# acquisition.net
KiCad netlist of a schematic drawn in Altium Designer
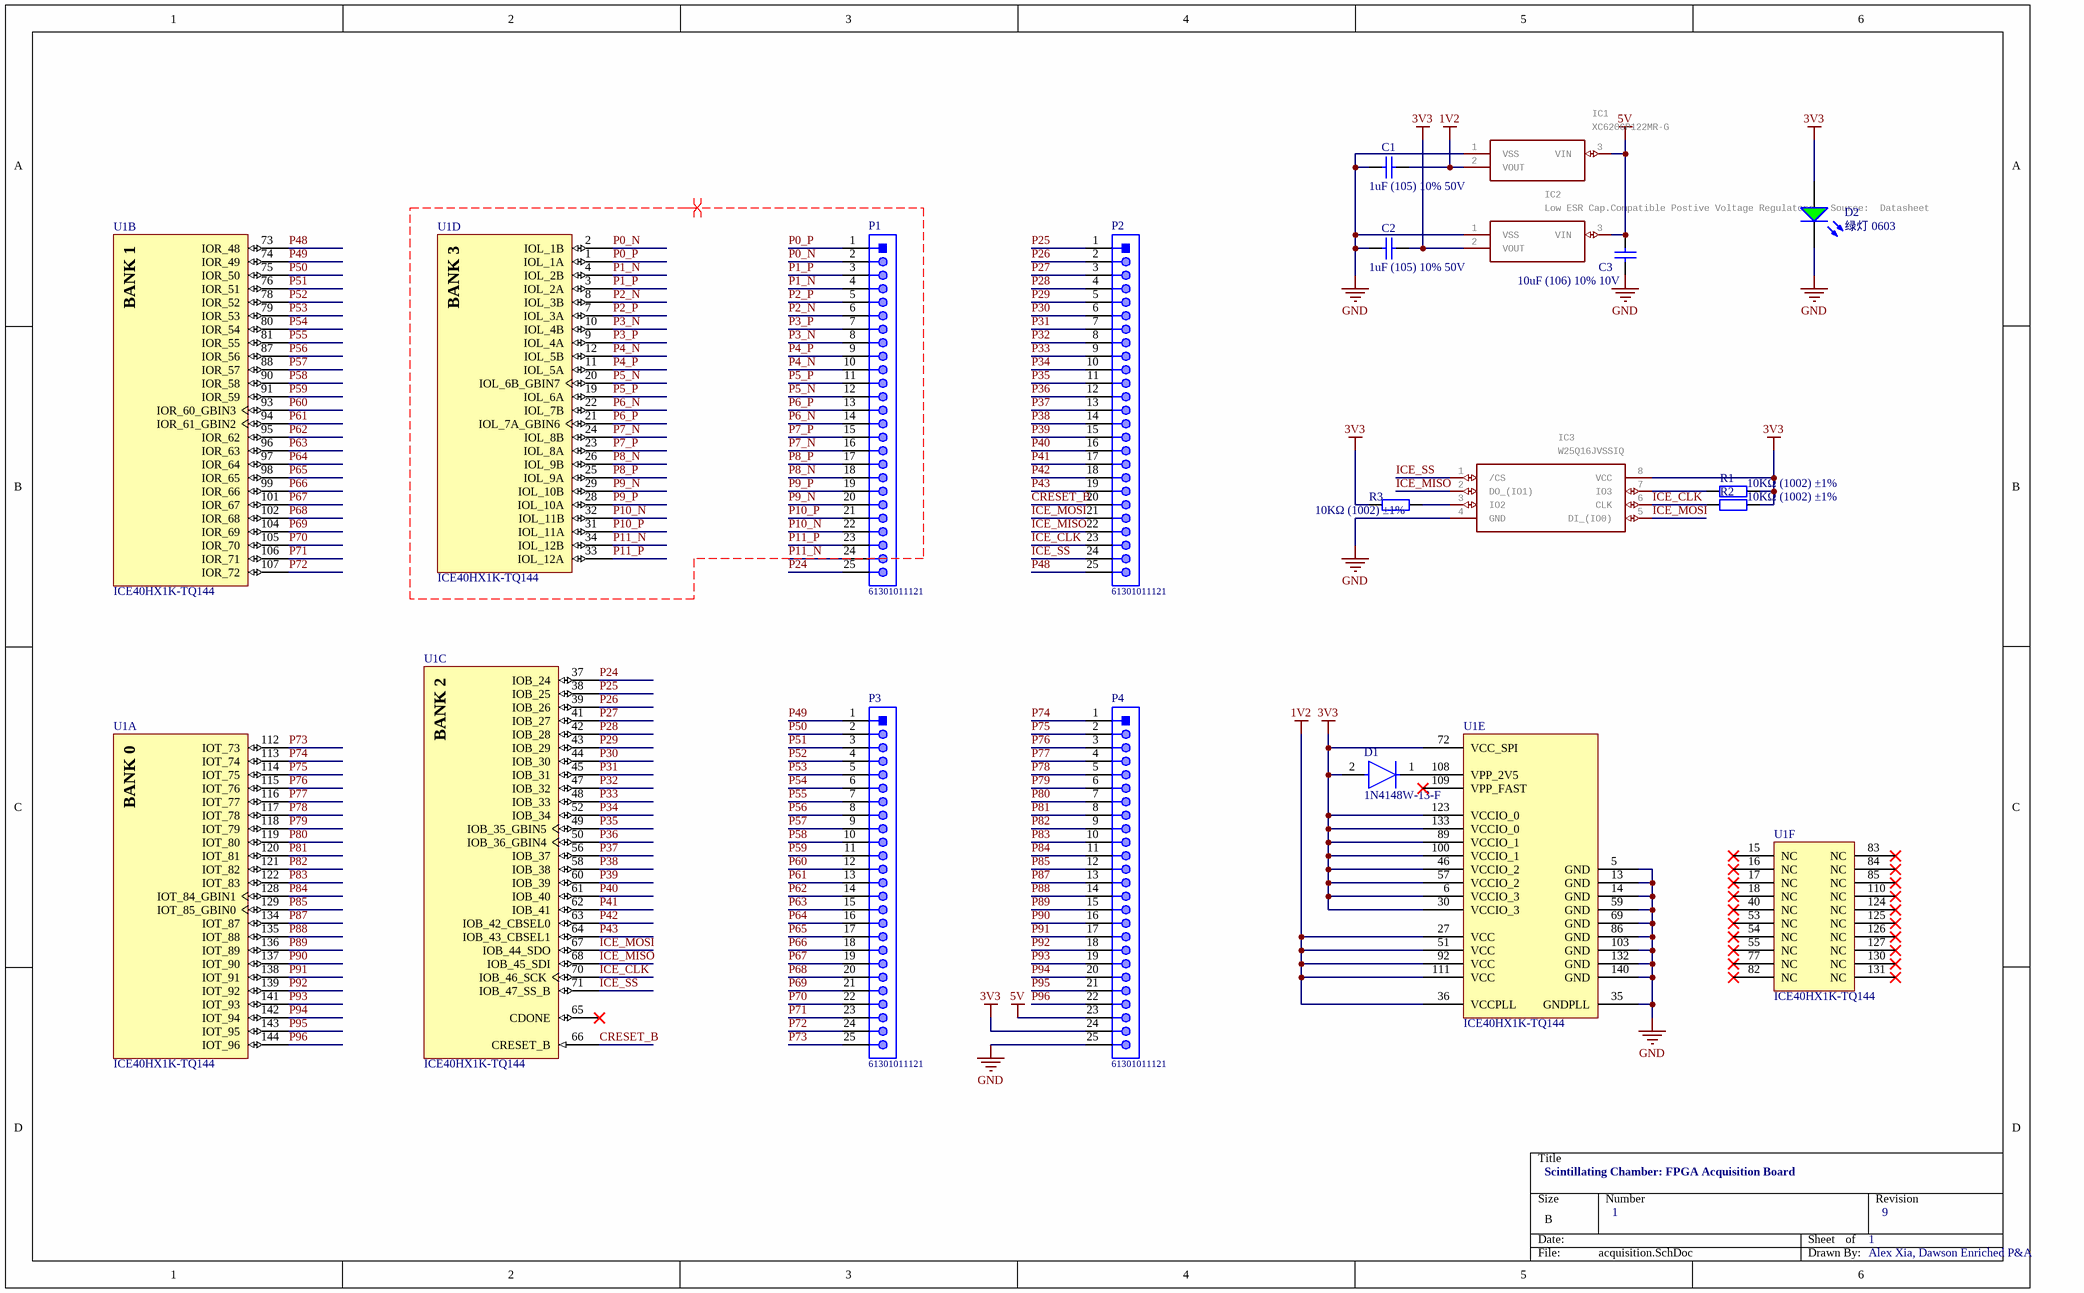
[diagram p0: acquisition.SchDoc]

(export (version "E")
  (design (tool "Eeschema 10.0.6"))
  (components
    (comp (ref "C1")
      (value "1uF (105) 10% 50V")
      (footprint "0603_C")
      (description "贴片电容")
      (libsource (lib "Cap") (part "0603 1uF (105) 10% 50V"))
    )
    (comp (ref "C2")
      (value "1uF (105) 10% 50V")
      (footprint "0603_C")
      (description "贴片电容")
      (libsource (lib "Cap") (part "0603 1uF (105) 10% 50V"))
    )
    (comp (ref "C3")
      (value "10uF (106) 10% 10V")
      (footprint "0603_C")
      (description "贴片电容")
      (libsource (lib "Cap") (part "0603 10uF (106) 10% 10V"))
    )
    (comp (ref "D1")
      (value "1N4148W-13-F")
      (footprint "FP-SOD123-MFG")
      (description "DIODE GEN PURP 100V 150MA SOD123")
      (fields
        (field (name "OCTOPART") "https://octopart.com/1n4148w-13-f-diodes+inc.-2359612")
        (field (name "MANUFACTURER") "Diodes Inc.")
      )
      (libsource (lib "Altium Content Vault") (part "d7152d700b627762746794eb795d46e"))
    )
    (comp (ref "D2")
      (value "绿灯 0603")
      (footprint "0603_LED_S1")
      (description "发光二极管")
      (libsource (lib "LED") (part "0603 绿灯"))
    )
    (comp (ref "IC1")
      (value "XC6206P122MR-G")
      (footprint "SOT95P280X130-3N")
      (fields (field (name "MOUSER_PART_NUMBER") "865-XC6206P122MR-G"))
      (libsource (lib "XC6206P122MR-G") (part "XC6206P122MR-G"))
    )
    (comp (ref "IC2")
      (value "Low ESR Cap.Compatible Postive Voltage Regulators   Source:  Datasheet")
      (footprint "SOT95P280X130-3N")
      (fields (field (name "MANUFACTURER_PART_NUMBER") "XC6206P332MR"))
      (libsource (lib "XC6206P332MR") (part "XC6206P332MR"))
    )
    (comp (ref "IC3")
      (value "W25Q16JVSSIQ")
      (footprint "SOIC127P790X216-8N")
      (fields (field (name "MOUSER_PART_NUMBER") "454-W25Q16JVSSIQ"))
      (libsource (lib "W25Q16JVSSIQ") (part "W25Q16JVSSIQ"))
    )
    (comp (ref "P1")
      (value "61301011121")
      (footprint "61301011121")
      (description "THT Vertical Pin Header WR-PHD, Pitch 2.54 mm, Single Row, 25 pins")
      (libsource (lib "headers") (part "header"))
    )
    (comp (ref "P2")
      (value "61301011121")
      (footprint "61301011121")
      (description "THT Vertical Pin Header WR-PHD, Pitch 2.54 mm, Single Row, 25 pins")
      (libsource (lib "headers") (part "header"))
    )
    (comp (ref "P3")
      (value "61301011121")
      (footprint "61301011121")
      (description "THT Vertical Pin Header WR-PHD, Pitch 2.54 mm, Single Row, 25 pins")
      (libsource (lib "headers") (part "header"))
    )
    (comp (ref "P4")
      (value "61301011121")
      (footprint "61301011121")
      (description "THT Vertical Pin Header WR-PHD, Pitch 2.54 mm, Single Row, 25 pins")
      (libsource (lib "headers") (part "header"))
    )
    (comp (ref "R1")
      (value "10KΩ (1002) ±1%")
      (footprint "0603_R")
      (description "贴片电阻")
      (libsource (lib "RES") (part "0603 10KΩ (1002) 1%"))
    )
    (comp (ref "R2")
      (value "10KΩ (1002) ±1%")
      (footprint "0603_R")
      (description "贴片电阻")
      (libsource (lib "RES") (part "0603 10KΩ (1002) 1%"))
    )
    (comp (ref "R3")
      (value "10KΩ (1002) ±1%")
      (footprint "0603_R")
      (description "贴片电阻")
      (libsource (lib "RES") (part "0603 10KΩ (1002) 1%"))
    )
    (comp (ref "U1")
      (value "ICE40HX1K-TQ144")
      (footprint "LATC-TQFP-144_L")
      (fields (field (name "MANUFACTURER") "Lattice Semiconductor"))
      (libsource (lib "Altium Content Vault") (part "LATC-HX1K-TQFP-144"))
    )
  )
  (nets
    (net (code "1") (name "/CRESET_B") (class "Default")
      (node (ref "P2") (pin "20") (pinfunction "20_20") (pintype "passive"))
      (node (ref "U1") (pin "66") (pinfunction "CRESET_B_66") (pintype "input"))
    )
    (net (code "2") (name "/ICE_CLK") (class "Default")
      (node (ref "IC3") (pin "6") (pinfunction "CLK_6") (pintype "bidirectional"))
      (node (ref "P2") (pin "23") (pinfunction "23_23") (pintype "passive"))
      (node (ref "R2") (pin "1") (pinfunction "1_1") (pintype "passive"))
      (node (ref "U1") (pin "70") (pinfunction "IOB_46_SCK_70") (pintype "bidirectional"))
    )
    (net (code "3") (name "/ICE_MISO") (class "Default")
      (node (ref "IC3") (pin "2") (pinfunction "DO_(IO1)_2") (pintype "bidirectional"))
      (node (ref "P2") (pin "22") (pinfunction "22_22") (pintype "passive"))
      (node (ref "U1") (pin "68") (pinfunction "IOB_45_SDI_68") (pintype "bidirectional"))
    )
    (net (code "4") (name "/ICE_MOSI") (class "Default")
      (node (ref "IC3") (pin "5") (pinfunction "DI_(IO0)_5") (pintype "bidirectional"))
      (node (ref "P2") (pin "21") (pinfunction "21_21") (pintype "passive"))
      (node (ref "U1") (pin "67") (pinfunction "IOB_44_SDO_67") (pintype "bidirectional"))
    )
    (net (code "5") (name "/ICE_SS") (class "Default")
      (node (ref "IC3") (pin "1") (pinfunction "/CS_1") (pintype "bidirectional"))
      (node (ref "P2") (pin "24") (pinfunction "24_24") (pintype "passive"))
      (node (ref "U1") (pin "71") (pinfunction "IOB_47_SS_B_71") (pintype "bidirectional"))
    )
    (net (code "6") (name "/P0_N") (class "Default")
      (node (ref "P1") (pin "2") (pinfunction "2_2") (pintype "passive"))
      (node (ref "U1") (pin "2") (pinfunction "IOL_1B_2") (pintype "bidirectional"))
    )
    (net (code "7") (name "/P0_P") (class "Default")
      (node (ref "P1") (pin "1") (pinfunction "1_1") (pintype "passive"))
      (node (ref "U1") (pin "1") (pinfunction "IOL_1A_1") (pintype "bidirectional"))
    )
    (net (code "8") (name "/P1_N") (class "Default")
      (node (ref "P1") (pin "4") (pinfunction "4_4") (pintype "passive"))
      (node (ref "U1") (pin "4") (pinfunction "IOL_2B_4") (pintype "bidirectional"))
    )
    (net (code "9") (name "/P1_P") (class "Default")
      (node (ref "P1") (pin "3") (pinfunction "3_3") (pintype "passive"))
      (node (ref "U1") (pin "3") (pinfunction "IOL_2A_3") (pintype "bidirectional"))
    )
    (net (code "10") (name "/P2_N") (class "Default")
      (node (ref "P1") (pin "6") (pinfunction "6_6") (pintype "passive"))
      (node (ref "U1") (pin "8") (pinfunction "IOL_3B_8") (pintype "bidirectional"))
    )
    (net (code "11") (name "/P2_P") (class "Default")
      (node (ref "P1") (pin "5") (pinfunction "5_5") (pintype "passive"))
      (node (ref "U1") (pin "7") (pinfunction "IOL_3A_7") (pintype "bidirectional"))
    )
    (net (code "12") (name "/P3_N") (class "Default")
      (node (ref "P1") (pin "8") (pinfunction "8_8") (pintype "passive"))
      (node (ref "U1") (pin "10") (pinfunction "IOL_4B_10") (pintype "bidirectional"))
    )
    (net (code "13") (name "/P3_P") (class "Default")
      (node (ref "P1") (pin "7") (pinfunction "7_7") (pintype "passive"))
      (node (ref "U1") (pin "9") (pinfunction "IOL_4A_9") (pintype "bidirectional"))
    )
    (net (code "14") (name "/P4_N") (class "Default")
      (node (ref "P1") (pin "10") (pinfunction "10_10") (pintype "passive"))
      (node (ref "U1") (pin "12") (pinfunction "IOL_5B_12") (pintype "bidirectional"))
    )
    (net (code "15") (name "/P4_P") (class "Default")
      (node (ref "P1") (pin "9") (pinfunction "9_9") (pintype "passive"))
      (node (ref "U1") (pin "11") (pinfunction "IOL_5A_11") (pintype "bidirectional"))
    )
    (net (code "16") (name "/P5_N") (class "Default")
      (node (ref "P1") (pin "12") (pinfunction "12_12") (pintype "passive"))
      (node (ref "U1") (pin "20") (pinfunction "IOL_6B_GBIN7_20") (pintype "bidirectional"))
    )
    (net (code "17") (name "/P5_P") (class "Default")
      (node (ref "P1") (pin "11") (pinfunction "11_11") (pintype "passive"))
      (node (ref "U1") (pin "19") (pinfunction "IOL_6A_19") (pintype "bidirectional"))
    )
    (net (code "18") (name "/P6_N") (class "Default")
      (node (ref "P1") (pin "14") (pinfunction "14_14") (pintype "passive"))
      (node (ref "U1") (pin "22") (pinfunction "IOL_7B_22") (pintype "bidirectional"))
    )
    (net (code "19") (name "/P6_P") (class "Default")
      (node (ref "P1") (pin "13") (pinfunction "13_13") (pintype "passive"))
      (node (ref "U1") (pin "21") (pinfunction "IOL_7A_GBIN6_21") (pintype "bidirectional"))
    )
    (net (code "20") (name "/P7_N") (class "Default")
      (node (ref "P1") (pin "16") (pinfunction "16_16") (pintype "passive"))
      (node (ref "U1") (pin "24") (pinfunction "IOL_8B_24") (pintype "bidirectional"))
    )
    (net (code "21") (name "/P7_P") (class "Default")
      (node (ref "P1") (pin "15") (pinfunction "15_15") (pintype "passive"))
      (node (ref "U1") (pin "23") (pinfunction "IOL_8A_23") (pintype "bidirectional"))
    )
    (net (code "22") (name "/P8_N") (class "Default")
      (node (ref "P1") (pin "18") (pinfunction "18_18") (pintype "passive"))
      (node (ref "U1") (pin "26") (pinfunction "IOL_9B_26") (pintype "bidirectional"))
    )
    (net (code "23") (name "/P8_P") (class "Default")
      (node (ref "P1") (pin "17") (pinfunction "17_17") (pintype "passive"))
      (node (ref "U1") (pin "25") (pinfunction "IOL_9A_25") (pintype "bidirectional"))
    )
    (net (code "24") (name "/P9_N") (class "Default")
      (node (ref "P1") (pin "20") (pinfunction "20_20") (pintype "passive"))
      (node (ref "U1") (pin "29") (pinfunction "IOL_10B_29") (pintype "bidirectional"))
    )
    (net (code "25") (name "/P9_P") (class "Default")
      (node (ref "P1") (pin "19") (pinfunction "19_19") (pintype "passive"))
      (node (ref "U1") (pin "28") (pinfunction "IOL_10A_28") (pintype "bidirectional"))
    )
    (net (code "26") (name "/P10_N") (class "Default")
      (node (ref "P1") (pin "22") (pinfunction "22_22") (pintype "passive"))
      (node (ref "U1") (pin "32") (pinfunction "IOL_11B_32") (pintype "bidirectional"))
    )
    (net (code "27") (name "/P10_P") (class "Default")
      (node (ref "P1") (pin "21") (pinfunction "21_21") (pintype "passive"))
      (node (ref "U1") (pin "31") (pinfunction "IOL_11A_31") (pintype "bidirectional"))
    )
    (net (code "28") (name "/P11_N") (class "Default")
      (node (ref "P1") (pin "24") (pinfunction "24_24") (pintype "passive"))
      (node (ref "U1") (pin "34") (pinfunction "IOL_12B_34") (pintype "bidirectional"))
    )
    (net (code "29") (name "/P11_P") (class "Default")
      (node (ref "P1") (pin "23") (pinfunction "23_23") (pintype "passive"))
      (node (ref "U1") (pin "33") (pinfunction "IOL_12A_33") (pintype "bidirectional"))
    )
    (net (code "30") (name "/P24") (class "Default")
      (node (ref "P1") (pin "25") (pinfunction "25_25") (pintype "passive"))
      (node (ref "U1") (pin "37") (pinfunction "IOB_24_37") (pintype "bidirectional"))
    )
    (net (code "31") (name "/P25") (class "Default")
      (node (ref "P2") (pin "1") (pinfunction "1_1") (pintype "passive"))
      (node (ref "U1") (pin "38") (pinfunction "IOB_25_38") (pintype "bidirectional"))
    )
    (net (code "32") (name "/P26") (class "Default")
      (node (ref "P2") (pin "2") (pinfunction "2_2") (pintype "passive"))
      (node (ref "U1") (pin "39") (pinfunction "IOB_26_39") (pintype "bidirectional"))
    )
    (net (code "33") (name "/P27") (class "Default")
      (node (ref "P2") (pin "3") (pinfunction "3_3") (pintype "passive"))
      (node (ref "U1") (pin "41") (pinfunction "IOB_27_41") (pintype "bidirectional"))
    )
    (net (code "34") (name "/P28") (class "Default")
      (node (ref "P2") (pin "4") (pinfunction "4_4") (pintype "passive"))
      (node (ref "U1") (pin "42") (pinfunction "IOB_28_42") (pintype "bidirectional"))
    )
    (net (code "35") (name "/P29") (class "Default")
      (node (ref "P2") (pin "5") (pinfunction "5_5") (pintype "passive"))
      (node (ref "U1") (pin "43") (pinfunction "IOB_29_43") (pintype "bidirectional"))
    )
    (net (code "36") (name "/P30") (class "Default")
      (node (ref "P2") (pin "6") (pinfunction "6_6") (pintype "passive"))
      (node (ref "U1") (pin "44") (pinfunction "IOB_30_44") (pintype "bidirectional"))
    )
    (net (code "37") (name "/P31") (class "Default")
      (node (ref "P2") (pin "7") (pinfunction "7_7") (pintype "passive"))
      (node (ref "U1") (pin "45") (pinfunction "IOB_31_45") (pintype "bidirectional"))
    )
    (net (code "38") (name "/P32") (class "Default")
      (node (ref "P2") (pin "8") (pinfunction "8_8") (pintype "passive"))
      (node (ref "U1") (pin "47") (pinfunction "IOB_32_47") (pintype "bidirectional"))
    )
    (net (code "39") (name "/P33") (class "Default")
      (node (ref "P2") (pin "9") (pinfunction "9_9") (pintype "passive"))
      (node (ref "U1") (pin "48") (pinfunction "IOB_33_48") (pintype "bidirectional"))
    )
    (net (code "40") (name "/P34") (class "Default")
      (node (ref "P2") (pin "10") (pinfunction "10_10") (pintype "passive"))
      (node (ref "U1") (pin "52") (pinfunction "IOB_34_52") (pintype "bidirectional"))
    )
    (net (code "41") (name "/P35") (class "Default")
      (node (ref "P2") (pin "11") (pinfunction "11_11") (pintype "passive"))
      (node (ref "U1") (pin "49") (pinfunction "IOB_35_GBIN5_49") (pintype "bidirectional"))
    )
    (net (code "42") (name "/P36") (class "Default")
      (node (ref "P2") (pin "12") (pinfunction "12_12") (pintype "passive"))
      (node (ref "U1") (pin "50") (pinfunction "IOB_36_GBIN4_50") (pintype "bidirectional"))
    )
    (net (code "43") (name "/P37") (class "Default")
      (node (ref "P2") (pin "13") (pinfunction "13_13") (pintype "passive"))
      (node (ref "U1") (pin "56") (pinfunction "IOB_37_56") (pintype "bidirectional"))
    )
    (net (code "44") (name "/P38") (class "Default")
      (node (ref "P2") (pin "14") (pinfunction "14_14") (pintype "passive"))
      (node (ref "U1") (pin "58") (pinfunction "IOB_38_58") (pintype "bidirectional"))
    )
    (net (code "45") (name "/P39") (class "Default")
      (node (ref "P2") (pin "15") (pinfunction "15_15") (pintype "passive"))
      (node (ref "U1") (pin "60") (pinfunction "IOB_39_60") (pintype "bidirectional"))
    )
    (net (code "46") (name "/P40") (class "Default")
      (node (ref "P2") (pin "16") (pinfunction "16_16") (pintype "passive"))
      (node (ref "U1") (pin "61") (pinfunction "IOB_40_61") (pintype "bidirectional"))
    )
    (net (code "47") (name "/P41") (class "Default")
      (node (ref "P2") (pin "17") (pinfunction "17_17") (pintype "passive"))
      (node (ref "U1") (pin "62") (pinfunction "IOB_41_62") (pintype "bidirectional"))
    )
    (net (code "48") (name "/P42") (class "Default")
      (node (ref "P2") (pin "18") (pinfunction "18_18") (pintype "passive"))
      (node (ref "U1") (pin "63") (pinfunction "IOB_42_CBSEL0_63") (pintype "bidirectional"))
    )
    (net (code "49") (name "/P43") (class "Default")
      (node (ref "P2") (pin "19") (pinfunction "19_19") (pintype "passive"))
      (node (ref "U1") (pin "64") (pinfunction "IOB_43_CBSEL1_64") (pintype "bidirectional"))
    )
    (net (code "50") (name "/P48") (class "Default")
      (node (ref "P2") (pin "25") (pinfunction "25_25") (pintype "passive"))
      (node (ref "U1") (pin "73") (pinfunction "IOR_48_73") (pintype "bidirectional"))
    )
    (net (code "51") (name "/P49") (class "Default")
      (node (ref "P3") (pin "1") (pinfunction "1_1") (pintype "passive"))
      (node (ref "U1") (pin "74") (pinfunction "IOR_49_74") (pintype "bidirectional"))
    )
    (net (code "52") (name "/P50") (class "Default")
      (node (ref "P3") (pin "2") (pinfunction "2_2") (pintype "passive"))
      (node (ref "U1") (pin "75") (pinfunction "IOR_50_75") (pintype "bidirectional"))
    )
    (net (code "53") (name "/P51") (class "Default")
      (node (ref "P3") (pin "3") (pinfunction "3_3") (pintype "passive"))
      (node (ref "U1") (pin "76") (pinfunction "IOR_51_76") (pintype "bidirectional"))
    )
    (net (code "54") (name "/P52") (class "Default")
      (node (ref "P3") (pin "4") (pinfunction "4_4") (pintype "passive"))
      (node (ref "U1") (pin "78") (pinfunction "IOR_52_78") (pintype "bidirectional"))
    )
    (net (code "55") (name "/P53") (class "Default")
      (node (ref "P3") (pin "5") (pinfunction "5_5") (pintype "passive"))
      (node (ref "U1") (pin "79") (pinfunction "IOR_53_79") (pintype "bidirectional"))
    )
    (net (code "56") (name "/P54") (class "Default")
      (node (ref "P3") (pin "6") (pinfunction "6_6") (pintype "passive"))
      (node (ref "U1") (pin "80") (pinfunction "IOR_54_80") (pintype "bidirectional"))
    )
    (net (code "57") (name "/P55") (class "Default")
      (node (ref "P3") (pin "7") (pinfunction "7_7") (pintype "passive"))
      (node (ref "U1") (pin "81") (pinfunction "IOR_55_81") (pintype "bidirectional"))
    )
    (net (code "58") (name "/P56") (class "Default")
      (node (ref "P3") (pin "8") (pinfunction "8_8") (pintype "passive"))
      (node (ref "U1") (pin "87") (pinfunction "IOR_56_87") (pintype "bidirectional"))
    )
    (net (code "59") (name "/P57") (class "Default")
      (node (ref "P3") (pin "9") (pinfunction "9_9") (pintype "passive"))
      (node (ref "U1") (pin "88") (pinfunction "IOR_57_88") (pintype "bidirectional"))
    )
    (net (code "60") (name "/P58") (class "Default")
      (node (ref "P3") (pin "10") (pinfunction "10_10") (pintype "passive"))
      (node (ref "U1") (pin "90") (pinfunction "IOR_58_90") (pintype "bidirectional"))
    )
    (net (code "61") (name "/P59") (class "Default")
      (node (ref "P3") (pin "11") (pinfunction "11_11") (pintype "passive"))
      (node (ref "U1") (pin "91") (pinfunction "IOR_59_91") (pintype "bidirectional"))
    )
    (net (code "62") (name "/P60") (class "Default")
      (node (ref "P3") (pin "12") (pinfunction "12_12") (pintype "passive"))
      (node (ref "U1") (pin "93") (pinfunction "IOR_60_GBIN3_93") (pintype "bidirectional"))
    )
    (net (code "63") (name "/P61") (class "Default")
      (node (ref "P3") (pin "13") (pinfunction "13_13") (pintype "passive"))
      (node (ref "U1") (pin "94") (pinfunction "IOR_61_GBIN2_94") (pintype "bidirectional"))
    )
    (net (code "64") (name "/P62") (class "Default")
      (node (ref "P3") (pin "14") (pinfunction "14_14") (pintype "passive"))
      (node (ref "U1") (pin "95") (pinfunction "IOR_62_95") (pintype "bidirectional"))
    )
    (net (code "65") (name "/P63") (class "Default")
      (node (ref "P3") (pin "15") (pinfunction "15_15") (pintype "passive"))
      (node (ref "U1") (pin "96") (pinfunction "IOR_63_96") (pintype "bidirectional"))
    )
    (net (code "66") (name "/P64") (class "Default")
      (node (ref "P3") (pin "16") (pinfunction "16_16") (pintype "passive"))
      (node (ref "U1") (pin "97") (pinfunction "IOR_64_97") (pintype "bidirectional"))
    )
    (net (code "67") (name "/P65") (class "Default")
      (node (ref "P3") (pin "17") (pinfunction "17_17") (pintype "passive"))
      (node (ref "U1") (pin "98") (pinfunction "IOR_65_98") (pintype "bidirectional"))
    )
    (net (code "68") (name "/P66") (class "Default")
      (node (ref "P3") (pin "18") (pinfunction "18_18") (pintype "passive"))
      (node (ref "U1") (pin "99") (pinfunction "IOR_66_99") (pintype "bidirectional"))
    )
    (net (code "69") (name "/P67") (class "Default")
      (node (ref "P3") (pin "19") (pinfunction "19_19") (pintype "passive"))
      (node (ref "U1") (pin "101") (pinfunction "IOR_67_101") (pintype "bidirectional"))
    )
    (net (code "70") (name "/P68") (class "Default")
      (node (ref "P3") (pin "20") (pinfunction "20_20") (pintype "passive"))
      (node (ref "U1") (pin "102") (pinfunction "IOR_68_102") (pintype "bidirectional"))
    )
    (net (code "71") (name "/P69") (class "Default")
      (node (ref "P3") (pin "21") (pinfunction "21_21") (pintype "passive"))
      (node (ref "U1") (pin "104") (pinfunction "IOR_69_104") (pintype "bidirectional"))
    )
    (net (code "72") (name "/P70") (class "Default")
      (node (ref "P3") (pin "22") (pinfunction "22_22") (pintype "passive"))
      (node (ref "U1") (pin "105") (pinfunction "IOR_70_105") (pintype "bidirectional"))
    )
    (net (code "73") (name "/P71") (class "Default")
      (node (ref "P3") (pin "23") (pinfunction "23_23") (pintype "passive"))
      (node (ref "U1") (pin "106") (pinfunction "IOR_71_106") (pintype "bidirectional"))
    )
    (net (code "74") (name "/P72") (class "Default")
      (node (ref "P3") (pin "24") (pinfunction "24_24") (pintype "passive"))
      (node (ref "U1") (pin "107") (pinfunction "IOR_72_107") (pintype "bidirectional"))
    )
    (net (code "75") (name "/P73") (class "Default")
      (node (ref "P3") (pin "25") (pinfunction "25_25") (pintype "passive"))
      (node (ref "U1") (pin "112") (pinfunction "IOT_73_112") (pintype "bidirectional"))
    )
    (net (code "76") (name "/P74") (class "Default")
      (node (ref "P4") (pin "1") (pinfunction "1_1") (pintype "passive"))
      (node (ref "U1") (pin "113") (pinfunction "IOT_74_113") (pintype "bidirectional"))
    )
    (net (code "77") (name "/P75") (class "Default")
      (node (ref "P4") (pin "2") (pinfunction "2_2") (pintype "passive"))
      (node (ref "U1") (pin "114") (pinfunction "IOT_75_114") (pintype "bidirectional"))
    )
    (net (code "78") (name "/P76") (class "Default")
      (node (ref "P4") (pin "3") (pinfunction "3_3") (pintype "passive"))
      (node (ref "U1") (pin "115") (pinfunction "IOT_76_115") (pintype "bidirectional"))
    )
    (net (code "79") (name "/P77") (class "Default")
      (node (ref "P4") (pin "4") (pinfunction "4_4") (pintype "passive"))
      (node (ref "U1") (pin "116") (pinfunction "IOT_77_116") (pintype "bidirectional"))
    )
    (net (code "80") (name "/P78") (class "Default")
      (node (ref "P4") (pin "5") (pinfunction "5_5") (pintype "passive"))
      (node (ref "U1") (pin "117") (pinfunction "IOT_78_117") (pintype "bidirectional"))
    )
    (net (code "81") (name "/P79") (class "Default")
      (node (ref "P4") (pin "6") (pinfunction "6_6") (pintype "passive"))
      (node (ref "U1") (pin "118") (pinfunction "IOT_79_118") (pintype "bidirectional"))
    )
    (net (code "82") (name "/P80") (class "Default")
      (node (ref "P4") (pin "7") (pinfunction "7_7") (pintype "passive"))
      (node (ref "U1") (pin "119") (pinfunction "IOT_80_119") (pintype "bidirectional"))
    )
    (net (code "83") (name "/P81") (class "Default")
      (node (ref "P4") (pin "8") (pinfunction "8_8") (pintype "passive"))
      (node (ref "U1") (pin "120") (pinfunction "IOT_81_120") (pintype "bidirectional"))
    )
    (net (code "84") (name "/P82") (class "Default")
      (node (ref "P4") (pin "9") (pinfunction "9_9") (pintype "passive"))
      (node (ref "U1") (pin "121") (pinfunction "IOT_82_121") (pintype "bidirectional"))
    )
    (net (code "85") (name "/P83") (class "Default")
      (node (ref "P4") (pin "10") (pinfunction "10_10") (pintype "passive"))
      (node (ref "U1") (pin "122") (pinfunction "IOT_83_122") (pintype "bidirectional"))
    )
    (net (code "86") (name "/P84") (class "Default")
      (node (ref "P4") (pin "11") (pinfunction "11_11") (pintype "passive"))
      (node (ref "U1") (pin "128") (pinfunction "IOT_84_GBIN1_128") (pintype "bidirectional"))
    )
    (net (code "87") (name "/P85") (class "Default")
      (node (ref "P4") (pin "12") (pinfunction "12_12") (pintype "passive"))
      (node (ref "U1") (pin "129") (pinfunction "IOT_85_GBIN0_129") (pintype "bidirectional"))
    )
    (net (code "88") (name "/P87") (class "Default")
      (node (ref "P4") (pin "13") (pinfunction "13_13") (pintype "passive"))
      (node (ref "U1") (pin "134") (pinfunction "IOT_87_134") (pintype "bidirectional"))
    )
    (net (code "89") (name "/P88") (class "Default")
      (node (ref "P4") (pin "14") (pinfunction "14_14") (pintype "passive"))
      (node (ref "U1") (pin "135") (pinfunction "IOT_88_135") (pintype "bidirectional"))
    )
    (net (code "90") (name "/P89") (class "Default")
      (node (ref "P4") (pin "15") (pinfunction "15_15") (pintype "passive"))
      (node (ref "U1") (pin "136") (pinfunction "IOT_89_136") (pintype "bidirectional"))
    )
    (net (code "91") (name "/P90") (class "Default")
      (node (ref "P4") (pin "16") (pinfunction "16_16") (pintype "passive"))
      (node (ref "U1") (pin "137") (pinfunction "IOT_90_137") (pintype "bidirectional"))
    )
    (net (code "92") (name "/P91") (class "Default")
      (node (ref "P4") (pin "17") (pinfunction "17_17") (pintype "passive"))
      (node (ref "U1") (pin "138") (pinfunction "IOT_91_138") (pintype "bidirectional"))
    )
    (net (code "93") (name "/P92") (class "Default")
      (node (ref "P4") (pin "18") (pinfunction "18_18") (pintype "passive"))
      (node (ref "U1") (pin "139") (pinfunction "IOT_92_139") (pintype "bidirectional"))
    )
    (net (code "94") (name "/P93") (class "Default")
      (node (ref "P4") (pin "19") (pinfunction "19_19") (pintype "passive"))
      (node (ref "U1") (pin "141") (pinfunction "IOT_93_141") (pintype "bidirectional"))
    )
    (net (code "95") (name "/P94") (class "Default")
      (node (ref "P4") (pin "20") (pinfunction "20_20") (pintype "passive"))
      (node (ref "U1") (pin "142") (pinfunction "IOT_94_142") (pintype "bidirectional"))
    )
    (net (code "96") (name "/P95") (class "Default")
      (node (ref "P4") (pin "21") (pinfunction "21_21") (pintype "passive"))
      (node (ref "U1") (pin "143") (pinfunction "IOT_95_143") (pintype "bidirectional"))
    )
    (net (code "97") (name "/P96") (class "Default")
      (node (ref "P4") (pin "22") (pinfunction "22_22") (pintype "passive"))
      (node (ref "U1") (pin "144") (pinfunction "IOT_96_144") (pintype "bidirectional"))
    )
    (net (code "98") (name "1V2") (class "Default")
      (node (ref "C1") (pin "1") (pinfunction "1_1") (pintype "passive"))
      (node (ref "IC1") (pin "2") (pinfunction "VOUT_2") (pintype "passive"))
      (node (ref "U1") (pin "111") (pinfunction "VCC_111") (pintype "power_in"))
      (node (ref "U1") (pin "27") (pinfunction "VCC_27") (pintype "power_in"))
      (node (ref "U1") (pin "36") (pinfunction "VCCPLL_36") (pintype "power_in"))
      (node (ref "U1") (pin "51") (pinfunction "VCC_51") (pintype "power_in"))
      (node (ref "U1") (pin "92") (pinfunction "VCC_92") (pintype "power_in"))
    )
    (net (code "99") (name "3V3") (class "Default")
      (node (ref "C2") (pin "1") (pinfunction "1_1") (pintype "passive"))
      (node (ref "D1") (pin "2") (pinfunction "A_2") (pintype "passive"))
      (node (ref "D2") (pin "A") (pinfunction "A_A") (pintype "passive"))
      (node (ref "IC2") (pin "2") (pinfunction "VOUT_2") (pintype "passive"))
      (node (ref "IC3") (pin "8") (pinfunction "VCC_8") (pintype "passive"))
      (node (ref "P4") (pin "24") (pinfunction "24_24") (pintype "passive"))
      (node (ref "R1") (pin "2") (pinfunction "2_2") (pintype "passive"))
      (node (ref "R2") (pin "2") (pinfunction "2_2") (pintype "passive"))
      (node (ref "R3") (pin "1") (pinfunction "1_1") (pintype "passive"))
      (node (ref "U1") (pin "100") (pinfunction "VCCIO_1_100") (pintype "power_in"))
      (node (ref "U1") (pin "123") (pinfunction "VCCIO_0_123") (pintype "power_in"))
      (node (ref "U1") (pin "133") (pinfunction "VCCIO_0_133") (pintype "power_in"))
      (node (ref "U1") (pin "30") (pinfunction "VCCIO_3_30") (pintype "power_in"))
      (node (ref "U1") (pin "46") (pinfunction "VCCIO_2_46") (pintype "power_in"))
      (node (ref "U1") (pin "57") (pinfunction "VCCIO_2_57") (pintype "power_in"))
      (node (ref "U1") (pin "6") (pinfunction "VCCIO_3_6") (pintype "power_in"))
      (node (ref "U1") (pin "72") (pinfunction "VCC_SPI_72") (pintype "power_in"))
      (node (ref "U1") (pin "89") (pinfunction "VCCIO_1_89") (pintype "power_in"))
    )
    (net (code "100") (name "5V") (class "Default")
      (node (ref "C3") (pin "1") (pinfunction "1_1") (pintype "passive"))
      (node (ref "IC1") (pin "3") (pinfunction "VIN_3") (pintype "bidirectional"))
      (node (ref "IC2") (pin "3") (pinfunction "VIN_3") (pintype "bidirectional"))
      (node (ref "P4") (pin "23") (pinfunction "23_23") (pintype "passive"))
    )
    (net (code "101") (name "GND") (class "Default")
      (node (ref "C1") (pin "2") (pinfunction "2_2") (pintype "passive"))
      (node (ref "C2") (pin "2") (pinfunction "2_2") (pintype "passive"))
      (node (ref "C3") (pin "2") (pinfunction "2_2") (pintype "passive"))
      (node (ref "D2") (pin "K") (pinfunction "K_K") (pintype "passive"))
      (node (ref "IC1") (pin "1") (pinfunction "VSS_1") (pintype "passive"))
      (node (ref "IC2") (pin "1") (pinfunction "VSS_1") (pintype "passive"))
      (node (ref "IC3") (pin "4") (pinfunction "GND_4") (pintype "passive"))
      (node (ref "P4") (pin "25") (pinfunction "25_25") (pintype "passive"))
      (node (ref "U1") (pin "103") (pinfunction "GND_103") (pintype "power_in"))
      (node (ref "U1") (pin "13") (pinfunction "GND_13") (pintype "power_in"))
      (node (ref "U1") (pin "132") (pinfunction "GND_132") (pintype "power_in"))
      (node (ref "U1") (pin "14") (pinfunction "GND_14") (pintype "power_in"))
      (node (ref "U1") (pin "140") (pinfunction "GND_140") (pintype "power_in"))
      (node (ref "U1") (pin "35") (pinfunction "GNDPLL_35") (pintype "power_in"))
      (node (ref "U1") (pin "5") (pinfunction "GND_5") (pintype "power_in"))
      (node (ref "U1") (pin "59") (pinfunction "GND_59") (pintype "power_in"))
      (node (ref "U1") (pin "69") (pinfunction "GND_69") (pintype "power_in"))
      (node (ref "U1") (pin "86") (pinfunction "GND_86") (pintype "power_in"))
    )
    (net (code "102") (name "Net-(D1-C)") (class "Default")
      (node (ref "D1") (pin "1") (pinfunction "C_1") (pintype "passive"))
      (node (ref "U1") (pin "108") (pinfunction "VPP_2V5_108") (pintype "power_in"))
    )
    (net (code "103") (name "Net-(IC3-IO2)") (class "Default")
      (node (ref "IC3") (pin "3") (pinfunction "IO2_3") (pintype "bidirectional"))
      (node (ref "R3") (pin "2") (pinfunction "2_2") (pintype "passive"))
    )
    (net (code "104") (name "Net-(IC3-IO3)") (class "Default")
      (node (ref "IC3") (pin "7") (pinfunction "IO3_7") (pintype "bidirectional"))
      (node (ref "R1") (pin "1") (pinfunction "1_1") (pintype "passive"))
    )
    (net (code "105") (name "unconnected-(U1C-CDONE-Pad65)") (class "Default")
      (node (ref "U1") (pin "65") (pinfunction "CDONE_65") (pintype "bidirectional+no_connect"))
    )
    (net (code "106") (name "unconnected-(U1E-VPP_FAST-Pad109)") (class "Default")
      (node (ref "U1") (pin "109") (pinfunction "VPP_FAST_109") (pintype "power_in+no_connect"))
    )
    (net (code "107") (name "unconnected-(U1F-NC-Pad15)") (class "Default")
      (node (ref "U1") (pin "15") (pinfunction "NC_15") (pintype "passive+no_connect"))
    )
    (net (code "108") (name "unconnected-(U1F-NC-Pad16)") (class "Default")
      (node (ref "U1") (pin "16") (pinfunction "NC_16") (pintype "passive+no_connect"))
    )
    (net (code "109") (name "unconnected-(U1F-NC-Pad17)") (class "Default")
      (node (ref "U1") (pin "17") (pinfunction "NC_17") (pintype "passive+no_connect"))
    )
    (net (code "110") (name "unconnected-(U1F-NC-Pad18)") (class "Default")
      (node (ref "U1") (pin "18") (pinfunction "NC_18") (pintype "passive+no_connect"))
    )
    (net (code "111") (name "unconnected-(U1F-NC-Pad40)") (class "Default")
      (node (ref "U1") (pin "40") (pinfunction "NC_40") (pintype "passive+no_connect"))
    )
    (net (code "112") (name "unconnected-(U1F-NC-Pad53)") (class "Default")
      (node (ref "U1") (pin "53") (pinfunction "NC_53") (pintype "passive+no_connect"))
    )
    (net (code "113") (name "unconnected-(U1F-NC-Pad54)") (class "Default")
      (node (ref "U1") (pin "54") (pinfunction "NC_54") (pintype "passive+no_connect"))
    )
    (net (code "114") (name "unconnected-(U1F-NC-Pad55)") (class "Default")
      (node (ref "U1") (pin "55") (pinfunction "NC_55") (pintype "passive+no_connect"))
    )
    (net (code "115") (name "unconnected-(U1F-NC-Pad77)") (class "Default")
      (node (ref "U1") (pin "77") (pinfunction "NC_77") (pintype "passive+no_connect"))
    )
    (net (code "116") (name "unconnected-(U1F-NC-Pad82)") (class "Default")
      (node (ref "U1") (pin "82") (pinfunction "NC_82") (pintype "passive+no_connect"))
    )
    (net (code "117") (name "unconnected-(U1F-NC-Pad83)") (class "Default")
      (node (ref "U1") (pin "83") (pinfunction "NC_83") (pintype "passive+no_connect"))
    )
    (net (code "118") (name "unconnected-(U1F-NC-Pad84)") (class "Default")
      (node (ref "U1") (pin "84") (pinfunction "NC_84") (pintype "passive+no_connect"))
    )
    (net (code "119") (name "unconnected-(U1F-NC-Pad85)") (class "Default")
      (node (ref "U1") (pin "85") (pinfunction "NC_85") (pintype "passive+no_connect"))
    )
    (net (code "120") (name "unconnected-(U1F-NC-Pad110)") (class "Default")
      (node (ref "U1") (pin "110") (pinfunction "NC_110") (pintype "passive+no_connect"))
    )
    (net (code "121") (name "unconnected-(U1F-NC-Pad124)") (class "Default")
      (node (ref "U1") (pin "124") (pinfunction "NC_124") (pintype "passive+no_connect"))
    )
    (net (code "122") (name "unconnected-(U1F-NC-Pad125)") (class "Default")
      (node (ref "U1") (pin "125") (pinfunction "NC_125") (pintype "passive+no_connect"))
    )
    (net (code "123") (name "unconnected-(U1F-NC-Pad126)") (class "Default")
      (node (ref "U1") (pin "126") (pinfunction "NC_126") (pintype "passive+no_connect"))
    )
    (net (code "124") (name "unconnected-(U1F-NC-Pad127)") (class "Default")
      (node (ref "U1") (pin "127") (pinfunction "NC_127") (pintype "passive+no_connect"))
    )
    (net (code "125") (name "unconnected-(U1F-NC-Pad130)") (class "Default")
      (node (ref "U1") (pin "130") (pinfunction "NC_130") (pintype "passive+no_connect"))
    )
    (net (code "126") (name "unconnected-(U1F-NC-Pad131)") (class "Default")
      (node (ref "U1") (pin "131") (pinfunction "NC_131") (pintype "passive+no_connect"))
    )
  )
)
